# Solution_2.net
KiCad netlist of a schematic drawn in Altium Designer
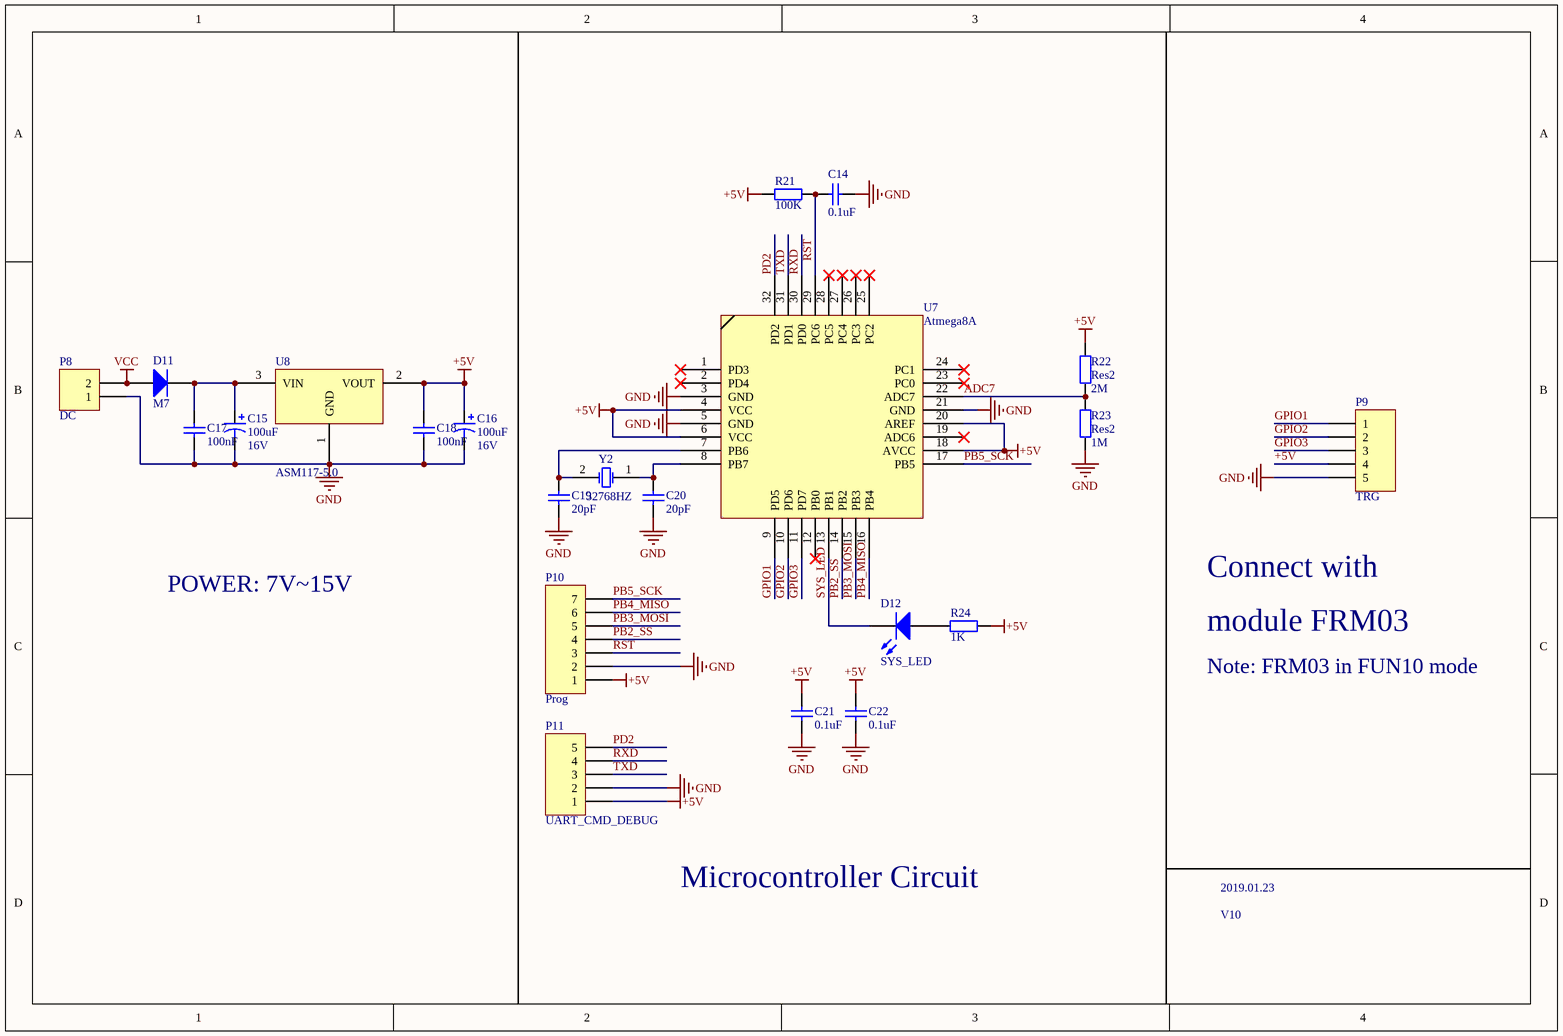
[diagram p0: Solution_2.SchDoc]

(export (version "E")
  (design (tool "Eeschema 10.0.6"))
  (components
    (comp (ref "C14")
      (value "0.1uF")
      (footprint "RAD-0.3")
      (description "Capacitor")
      (fields (field (name "PUBLISHER") "Altium Limited"))
      (libsource (lib "Miscellaneous Devices") (part "Cap"))
    )
    (comp (ref "C15")
      (value "100uF")
      (footprint "C0805")
      (description "Polarized Capacitor (Surface Mount)")
      (fields (field (name "ALTIUM_VALUE") "16V") (field (name "PUBLISHER") "Altium Limited"))
      (libsource (lib "Miscellaneous Devices") (part "Cap Pol3"))
    )
    (comp (ref "C16")
      (value "100uF")
      (footprint "C0805")
      (description "Polarized Capacitor (Surface Mount)")
      (fields (field (name "ALTIUM_VALUE") "16V") (field (name "PUBLISHER") "Altium Limited"))
      (libsource (lib "Miscellaneous Devices") (part "Cap Pol3"))
    )
    (comp (ref "C17")
      (value "100nF")
      (footprint "RAD-0.3")
      (description "Capacitor")
      (fields (field (name "PUBLISHER") "Altium Limited"))
      (libsource (lib "Miscellaneous Devices") (part "Cap"))
    )
    (comp (ref "C18")
      (value "100nF")
      (footprint "RAD-0.3")
      (description "Capacitor")
      (fields (field (name "PUBLISHER") "Altium Limited"))
      (libsource (lib "Miscellaneous Devices") (part "Cap"))
    )
    (comp (ref "C19")
      (value "20pF")
      (footprint "RAD-0.3")
      (description "Capacitor")
      (fields (field (name "PUBLISHER") "Altium Limited"))
      (libsource (lib "Miscellaneous Devices") (part "Cap"))
    )
    (comp (ref "C20")
      (value "20pF")
      (footprint "RAD-0.3")
      (description "Capacitor")
      (fields (field (name "PUBLISHER") "Altium Limited"))
      (libsource (lib "Miscellaneous Devices") (part "Cap"))
    )
    (comp (ref "C21")
      (value "0.1uF")
      (footprint "RAD-0.3")
      (description "Capacitor")
      (fields (field (name "PUBLISHER") "Altium Limited"))
      (libsource (lib "Miscellaneous Devices") (part "Cap"))
    )
    (comp (ref "C22")
      (value "0.1uF")
      (footprint "RAD-0.3")
      (description "Capacitor")
      (fields (field (name "PUBLISHER") "Altium Limited"))
      (libsource (lib "Miscellaneous Devices") (part "Cap"))
    )
    (comp (ref "D11")
      (value "M7")
      (footprint "SMC")
      (description "Default Diode")
      (fields (field (name "PUBLISHER") "Altium Limited"))
      (libsource (lib "Miscellaneous Devices") (part "Diode"))
    )
    (comp (ref "D12")
      (value "SYS_LED")
      (footprint "LED-0")
      (description "Typical INFRARED GaAs LED")
      (fields (field (name "PUBLISHER") "Altium Limited"))
      (libsource (lib "Miscellaneous Devices") (part "LED0"))
    )
    (comp (ref "P8")
      (value "DC")
      (footprint "HDR1X2")
      (description "Header, 2-Pin")
      (fields (field (name "PUBLISHER") "Altium Limited"))
      (libsource (lib "Miscellaneous Connectors") (part "Header 2"))
    )
    (comp (ref "P9")
      (value "TRG")
      (footprint "HDR1X5")
      (description "Header, 5-Pin")
      (fields (field (name "PUBLISHER") "Altium Limited"))
      (libsource (lib "Miscellaneous Connectors") (part "Header 5"))
    )
    (comp (ref "P10")
      (value "Prog")
      (footprint "HDR1X7")
      (description "Header, 7-Pin")
      (fields (field (name "PUBLISHER") "Altium Limited"))
      (libsource (lib "Miscellaneous Connectors") (part "Header 7"))
    )
    (comp (ref "P11")
      (value "UART_CMD_DEBUG")
      (footprint "HDR1X5")
      (description "Header, 5-Pin")
      (fields (field (name "PUBLISHER") "Altium Limited"))
      (libsource (lib "") (part "Header 5_1"))
    )
    (comp (ref "R21")
      (value "100K")
      (footprint "AXIAL-0.4")
      (description "Resistor")
      (fields (field (name "PUBLISHER") "Altium Limited"))
      (libsource (lib "") (part "Res2_1"))
    )
    (comp (ref "R22")
      (value "Res2")
      (footprint "AXIAL-0.4")
      (description "Resistor")
      (fields (field (name "ALTIUM_VALUE") "2M") (field (name "PUBLISHER") "Altium Limited"))
      (libsource (lib "Miscellaneous Devices") (part "Res2"))
    )
    (comp (ref "R23")
      (value "Res2")
      (footprint "AXIAL-0.4")
      (description "Resistor")
      (fields (field (name "ALTIUM_VALUE") "1M") (field (name "PUBLISHER") "Altium Limited"))
      (libsource (lib "Miscellaneous Devices") (part "Res2"))
    )
    (comp (ref "R24")
      (value "1K")
      (footprint "AXIAL-0.4")
      (description "Resistor")
      (fields (field (name "PUBLISHER") "Altium Limited"))
      (libsource (lib "") (part "Res2_1"))
    )
    (comp (ref "U7")
      (value "Atmega8A")
      (description "AVR 8bit microcontroller")
      (libsource (lib "Schlib1") (part "ATMEGA8A"))
    )
    (comp (ref "U8")
      (value "ASM117-5.0")
      (description "5V 1A LOW DROPOUT VOLTAGE REGULATOR")
      (libsource (lib "Schlib1") (part "ASM117-5.0"))
    )
    (comp (ref "Y2")
      (value "32768HZ")
      (footprint "R38")
      (description "Crystal Oscillator")
      (fields (field (name "PUBLISHER") "Altium Limited"))
      (libsource (lib "Miscellaneous Devices") (part "XTAL"))
    )
  )
  (nets
    (net (code "1") (name "+5V") (class "Default")
      (node (ref "C16") (pin "1") (pinfunction "1_1") (pintype "passive"))
      (node (ref "C18") (pin "2") (pinfunction "2_2") (pintype "passive"))
      (node (ref "C21") (pin "2") (pinfunction "2_2") (pintype "passive"))
      (node (ref "C22") (pin "2") (pinfunction "2_2") (pintype "passive"))
      (node (ref "P10") (pin "1") (pinfunction "1_1") (pintype "passive"))
      (node (ref "P11") (pin "1") (pinfunction "1_1") (pintype "passive"))
      (node (ref "P9") (pin "4") (pinfunction "4_4") (pintype "passive"))
      (node (ref "R21") (pin "1") (pinfunction "1_1") (pintype "passive"))
      (node (ref "R22") (pin "2") (pinfunction "2_2") (pintype "passive"))
      (node (ref "R24") (pin "2") (pinfunction "2_2") (pintype "passive"))
      (node (ref "U7") (pin "18") (pinfunction "AVCC_18") (pintype "passive"))
      (node (ref "U7") (pin "20") (pinfunction "AREF_20") (pintype "passive"))
      (node (ref "U7") (pin "4") (pinfunction "VCC_4") (pintype "passive"))
      (node (ref "U7") (pin "6") (pinfunction "VCC_6") (pintype "passive"))
      (node (ref "U8") (pin "2") (pinfunction "VOUT_2") (pintype "passive"))
    )
    (net (code "2") (name "/ADC7") (class "Default")
      (node (ref "R22") (pin "1") (pinfunction "1_1") (pintype "passive"))
      (node (ref "R23") (pin "2") (pinfunction "2_2") (pintype "passive"))
      (node (ref "U7") (pin "22") (pinfunction "ADC7_22") (pintype "passive"))
    )
    (net (code "3") (name "/GPIO1") (class "Default")
      (node (ref "P9") (pin "1") (pinfunction "1_1") (pintype "passive"))
      (node (ref "U7") (pin "9") (pinfunction "PD5_9") (pintype "passive"))
    )
    (net (code "4") (name "/GPIO2") (class "Default")
      (node (ref "P9") (pin "2") (pinfunction "2_2") (pintype "passive"))
      (node (ref "U7") (pin "10") (pinfunction "PD6_10") (pintype "passive"))
    )
    (net (code "5") (name "/GPIO3") (class "Default")
      (node (ref "P9") (pin "3") (pinfunction "3_3") (pintype "passive"))
      (node (ref "U7") (pin "11") (pinfunction "PD7_11") (pintype "passive"))
    )
    (net (code "6") (name "/PB2_SS") (class "Default")
      (node (ref "P10") (pin "4") (pinfunction "4_4") (pintype "passive"))
      (node (ref "U7") (pin "14") (pinfunction "PB2_14") (pintype "passive"))
    )
    (net (code "7") (name "/PB3_MOSI") (class "Default")
      (node (ref "P10") (pin "5") (pinfunction "5_5") (pintype "passive"))
      (node (ref "U7") (pin "15") (pinfunction "PB3_15") (pintype "passive"))
    )
    (net (code "8") (name "/PB4_MISO") (class "Default")
      (node (ref "P10") (pin "6") (pinfunction "6_6") (pintype "passive"))
      (node (ref "U7") (pin "16") (pinfunction "PB4_16") (pintype "passive"))
    )
    (net (code "9") (name "/PB5_SCK") (class "Default")
      (node (ref "P10") (pin "7") (pinfunction "7_7") (pintype "passive"))
      (node (ref "U7") (pin "17") (pinfunction "PB5_17") (pintype "passive"))
    )
    (net (code "10") (name "/PD2") (class "Default")
      (node (ref "P11") (pin "5") (pinfunction "5_5") (pintype "passive"))
      (node (ref "U7") (pin "32") (pinfunction "PD2_32") (pintype "passive"))
    )
    (net (code "11") (name "/RST") (class "Default")
      (node (ref "C14") (pin "2") (pinfunction "2_2") (pintype "passive"))
      (node (ref "P10") (pin "3") (pinfunction "3_3") (pintype "passive"))
      (node (ref "R21") (pin "2") (pinfunction "2_2") (pintype "passive"))
      (node (ref "U7") (pin "29") (pinfunction "PC6_29") (pintype "passive"))
    )
    (net (code "12") (name "/RXD") (class "Default")
      (node (ref "P11") (pin "4") (pinfunction "4_4") (pintype "passive"))
      (node (ref "U7") (pin "30") (pinfunction "PD0_30") (pintype "passive"))
    )
    (net (code "13") (name "/SYS_LED") (class "Default")
      (node (ref "D12") (pin "2") (pinfunction "K_2") (pintype "passive"))
      (node (ref "U7") (pin "13") (pinfunction "PB1_13") (pintype "passive"))
    )
    (net (code "14") (name "/TXD") (class "Default")
      (node (ref "P11") (pin "3") (pinfunction "3_3") (pintype "passive"))
      (node (ref "U7") (pin "31") (pinfunction "PD1_31") (pintype "passive"))
    )
    (net (code "15") (name "GND") (class "Default")
      (node (ref "C14") (pin "1") (pinfunction "1_1") (pintype "passive"))
      (node (ref "C15") (pin "2") (pinfunction "2_2") (pintype "passive"))
      (node (ref "C16") (pin "2") (pinfunction "2_2") (pintype "passive"))
      (node (ref "C17") (pin "1") (pinfunction "1_1") (pintype "passive"))
      (node (ref "C18") (pin "1") (pinfunction "1_1") (pintype "passive"))
      (node (ref "C19") (pin "1") (pinfunction "1_1") (pintype "passive"))
      (node (ref "C20") (pin "1") (pinfunction "1_1") (pintype "passive"))
      (node (ref "C21") (pin "1") (pinfunction "1_1") (pintype "passive"))
      (node (ref "C22") (pin "1") (pinfunction "1_1") (pintype "passive"))
      (node (ref "P10") (pin "2") (pinfunction "2_2") (pintype "passive"))
      (node (ref "P11") (pin "2") (pinfunction "2_2") (pintype "passive"))
      (node (ref "P8") (pin "1") (pinfunction "1_1") (pintype "passive"))
      (node (ref "P9") (pin "5") (pinfunction "5_5") (pintype "passive"))
      (node (ref "R23") (pin "1") (pinfunction "1_1") (pintype "passive"))
      (node (ref "U7") (pin "21") (pinfunction "GND_21") (pintype "passive"))
      (node (ref "U7") (pin "3") (pinfunction "GND_3") (pintype "passive"))
      (node (ref "U7") (pin "5") (pinfunction "GND_5") (pintype "passive"))
      (node (ref "U8") (pin "1") (pinfunction "GND_1") (pintype "passive"))
    )
    (net (code "16") (name "Net-(D11-K)") (class "Default")
      (node (ref "C15") (pin "1") (pinfunction "1_1") (pintype "passive"))
      (node (ref "C17") (pin "2") (pinfunction "2_2") (pintype "passive"))
      (node (ref "D11") (pin "2") (pinfunction "K_2") (pintype "passive"))
      (node (ref "U8") (pin "3") (pinfunction "VIN_3") (pintype "passive"))
    )
    (net (code "17") (name "Net-(D12-A)") (class "Default")
      (node (ref "D12") (pin "1") (pinfunction "A_1") (pintype "passive"))
      (node (ref "R24") (pin "1") (pinfunction "1_1") (pintype "passive"))
    )
    (net (code "18") (name "Net-(U7-PB6)") (class "Default")
      (node (ref "C19") (pin "2") (pinfunction "2_2") (pintype "passive"))
      (node (ref "U7") (pin "7") (pinfunction "PB6_7") (pintype "passive"))
      (node (ref "Y2") (pin "2") (pinfunction "OSC2_2") (pintype "passive"))
    )
    (net (code "19") (name "Net-(U7-PB7)") (class "Default")
      (node (ref "C20") (pin "2") (pinfunction "2_2") (pintype "passive"))
      (node (ref "U7") (pin "8") (pinfunction "PB7_8") (pintype "passive"))
      (node (ref "Y2") (pin "1") (pinfunction "OSC1_1") (pintype "passive"))
    )
    (net (code "20") (name "VCC") (class "Default")
      (node (ref "D11") (pin "1") (pinfunction "A_1") (pintype "passive"))
      (node (ref "P8") (pin "2") (pinfunction "2_2") (pintype "passive"))
    )
    (net (code "21") (name "unconnected-(U7-ADC6-Pad19)") (class "Default")
      (node (ref "U7") (pin "19") (pinfunction "ADC6_19") (pintype "passive+no_connect"))
    )
    (net (code "22") (name "unconnected-(U7-PB0-Pad12)") (class "Default")
      (node (ref "U7") (pin "12") (pinfunction "PB0_12") (pintype "passive+no_connect"))
    )
    (net (code "23") (name "unconnected-(U7-PC0-Pad23)") (class "Default")
      (node (ref "U7") (pin "23") (pinfunction "PC0_23") (pintype "passive+no_connect"))
    )
    (net (code "24") (name "unconnected-(U7-PC1-Pad24)") (class "Default")
      (node (ref "U7") (pin "24") (pinfunction "PC1_24") (pintype "passive+no_connect"))
    )
    (net (code "25") (name "unconnected-(U7-PC2-Pad25)") (class "Default")
      (node (ref "U7") (pin "25") (pinfunction "PC2_25") (pintype "passive+no_connect"))
    )
    (net (code "26") (name "unconnected-(U7-PC3-Pad26)") (class "Default")
      (node (ref "U7") (pin "26") (pinfunction "PC3_26") (pintype "passive+no_connect"))
    )
    (net (code "27") (name "unconnected-(U7-PC4-Pad27)") (class "Default")
      (node (ref "U7") (pin "27") (pinfunction "PC4_27") (pintype "passive+no_connect"))
    )
    (net (code "28") (name "unconnected-(U7-PC5-Pad28)") (class "Default")
      (node (ref "U7") (pin "28") (pinfunction "PC5_28") (pintype "passive+no_connect"))
    )
    (net (code "29") (name "unconnected-(U7-PD3-Pad1)") (class "Default")
      (node (ref "U7") (pin "1") (pinfunction "PD3_1") (pintype "passive+no_connect"))
    )
    (net (code "30") (name "unconnected-(U7-PD4-Pad2)") (class "Default")
      (node (ref "U7") (pin "2") (pinfunction "PD4_2") (pintype "passive+no_connect"))
    )
  )
)
